# 5_ADC.net
KiCad netlist of a schematic drawn in Altium Designer
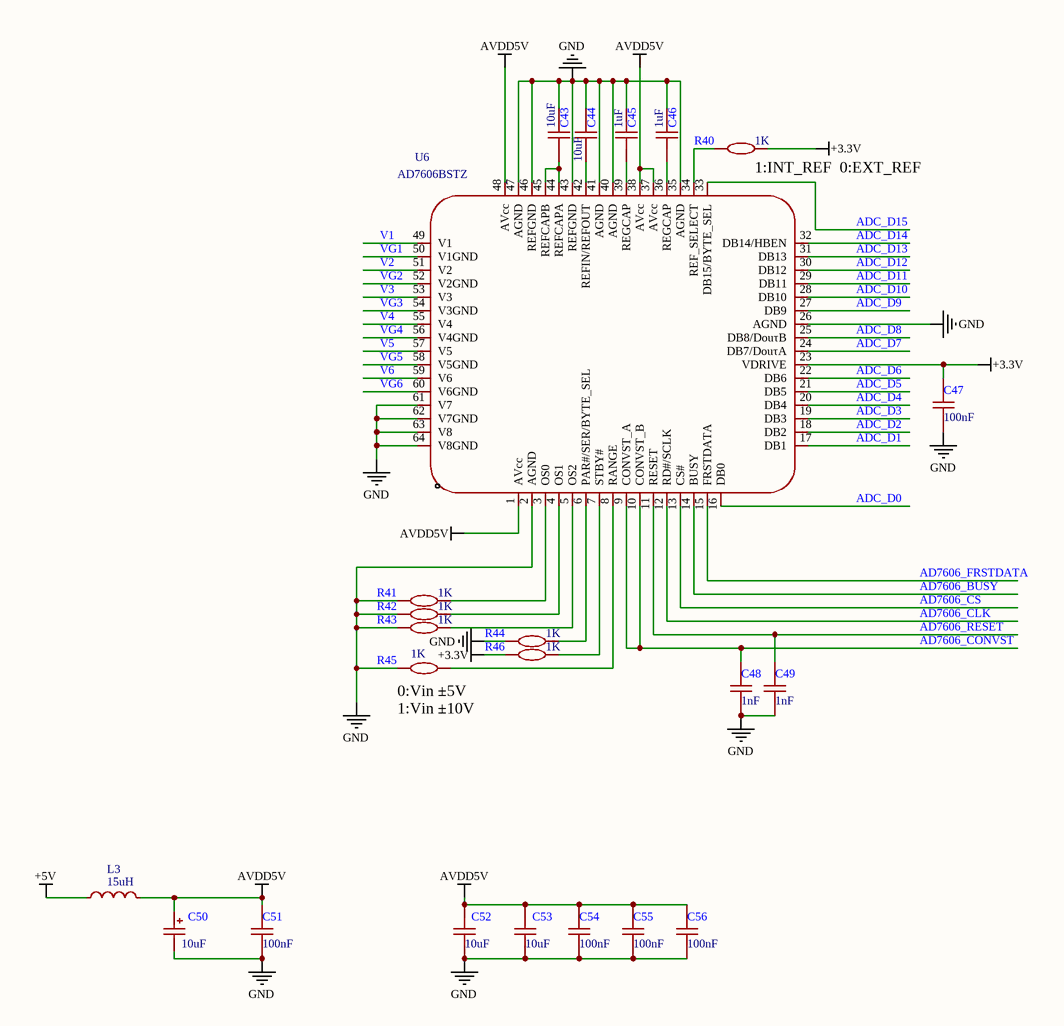
[diagram p0: 5_ADC.schdoc]

(export (version "E")
  (design (tool "Eeschema 10.0.6"))
  (components
    (comp (ref "C43") (value "10uF") (footprint "C0805") (libsource (lib "34567890") (part "CAP_0805")))
    (comp (ref "C44") (value "10uF") (footprint "C0805") (libsource (lib "34567890") (part "CAP_0805")))
    (comp (ref "C45") (value "1uF") (footprint "C0603") (libsource (lib "34567890") (part "CAP_0603")))
    (comp (ref "C46") (value "1uF") (footprint "C0603") (libsource (lib "34567890") (part "CAP_0603")))
    (comp (ref "C47") (value "100nF") (footprint "C0603") (libsource (lib "34567890") (part "CAP_0603")))
    (comp (ref "C48") (value "1nF") (footprint "C0603") (libsource (lib "34567890") (part "CAP_0603")))
    (comp (ref "C49") (value "1nF") (footprint "C0603") (libsource (lib "34567890") (part "CAP_0603")))
    (comp (ref "C50")
      (value "10uF")
      (footprint "C_Ele_SMD_3x5.4mm")
      (libsource (lib "34567890") (part "C_Ele_SMD_3x5.4mm"))
    )
    (comp (ref "C51") (value "100nF") (footprint "C0603") (libsource (lib "34567890") (part "CAP_0603")))
    (comp (ref "C52") (value "10uF") (footprint "C0805") (libsource (lib "34567890") (part "CAP_0805")))
    (comp (ref "C53") (value "10uF") (footprint "C0805") (libsource (lib "34567890") (part "CAP_0805")))
    (comp (ref "C54") (value "100nF") (footprint "C0603") (libsource (lib "34567890") (part "CAP_0603")))
    (comp (ref "C55") (value "100nF") (footprint "C0603") (libsource (lib "34567890") (part "CAP_0603")))
    (comp (ref "C56") (value "100nF") (footprint "C0603") (libsource (lib "34567890") (part "CAP_0603")))
    (comp (ref "L3")
      (value "15uH")
      (footprint "IND-SMD_L7.1-W6.6_SLO0618H")
      (libsource (lib "34567890") (part "SLO0630H150MTT"))
    )
    (comp (ref "R40") (value "1K") (footprint "R0603") (libsource (lib "34567890") (part "Res_0603")))
    (comp (ref "R41") (value "1K") (footprint "R0603") (libsource (lib "34567890") (part "Res_0603")))
    (comp (ref "R42") (value "1K") (footprint "R0603") (libsource (lib "34567890") (part "Res_0603")))
    (comp (ref "R43") (value "1K") (footprint "R0603") (libsource (lib "34567890") (part "Res_0603")))
    (comp (ref "R44") (value "1K") (footprint "R0603") (libsource (lib "34567890") (part "Res_0603")))
    (comp (ref "R45") (value "1K") (footprint "R0603") (libsource (lib "34567890") (part "Res_0603")))
    (comp (ref "R46") (value "1K") (footprint "R0603") (libsource (lib "34567890") (part "Res_0603")))
    (comp (ref "U6")
      (value "AD7606BSTZ")
      (footprint "LQFP-64_L10.0-W10.0-P0.50-LS12.0-BL")
      (libsource (lib "34567890") (part "AD7606BSTZ"))
    )
  )
  (nets
    (net (code "1") (name "+3.3V") (class "Default")
      (node (ref "C47") (pin "2") (pinfunction "2_2") (pintype "passive"))
      (node (ref "R40") (pin "2") (pinfunction "2_2") (pintype "passive"))
      (node (ref "R46") (pin "1") (pinfunction "1_1") (pintype "passive"))
      (node (ref "U6") (pin "23") (pinfunction "VDRIVE_23") (pintype "passive"))
    )
    (net (code "2") (name "+5V") (class "Default")
      (node (ref "L3") (pin "1") (pinfunction "1_1") (pintype "passive"))
    )
    (net (code "3") (name "/AD7606_BUSY") (class "Default")
      (node (ref "U6") (pin "14") (pinfunction "BUSY_14") (pintype "passive"))
    )
    (net (code "4") (name "/AD7606_CLK") (class "Default")
      (node (ref "U6") (pin "12") (pinfunction "RD#/SCLK_12") (pintype "passive"))
    )
    (net (code "5") (name "/AD7606_CONVST") (class "Default")
      (node (ref "C48") (pin "2") (pinfunction "2_2") (pintype "passive"))
      (node (ref "U6") (pin "10") (pinfunction "CONVST_B_10") (pintype "passive"))
      (node (ref "U6") (pin "9") (pinfunction "CONVST_A_9") (pintype "passive"))
    )
    (net (code "6") (name "/AD7606_CS") (class "Default")
      (node (ref "U6") (pin "13") (pinfunction "CS#_13") (pintype "passive"))
    )
    (net (code "7") (name "/AD7606_FRSTDATA") (class "Default")
      (node (ref "U6") (pin "15") (pinfunction "FRSTDATA_15") (pintype "passive"))
    )
    (net (code "8") (name "/AD7606_RESET") (class "Default")
      (node (ref "C49") (pin "2") (pinfunction "2_2") (pintype "passive"))
      (node (ref "U6") (pin "11") (pinfunction "RESET_11") (pintype "passive"))
    )
    (net (code "9") (name "/ADC_D0") (class "Default")
      (node (ref "U6") (pin "16") (pinfunction "DB0_16") (pintype "passive"))
    )
    (net (code "10") (name "/ADC_D1") (class "Default")
      (node (ref "U6") (pin "17") (pinfunction "DB1_17") (pintype "passive"))
    )
    (net (code "11") (name "/ADC_D2") (class "Default")
      (node (ref "U6") (pin "18") (pinfunction "DB2_18") (pintype "passive"))
    )
    (net (code "12") (name "/ADC_D3") (class "Default")
      (node (ref "U6") (pin "19") (pinfunction "DB3_19") (pintype "passive"))
    )
    (net (code "13") (name "/ADC_D4") (class "Default")
      (node (ref "U6") (pin "20") (pinfunction "DB4_20") (pintype "passive"))
    )
    (net (code "14") (name "/ADC_D5") (class "Default")
      (node (ref "U6") (pin "21") (pinfunction "DB5_21") (pintype "passive"))
    )
    (net (code "15") (name "/ADC_D6") (class "Default")
      (node (ref "U6") (pin "22") (pinfunction "DB6_22") (pintype "passive"))
    )
    (net (code "16") (name "/ADC_D7") (class "Default")
      (node (ref "U6") (pin "24") (pinfunction "DB7/DouτA_24") (pintype "passive"))
    )
    (net (code "17") (name "/ADC_D8") (class "Default")
      (node (ref "U6") (pin "25") (pinfunction "DB8/DouτB_25") (pintype "passive"))
    )
    (net (code "18") (name "/ADC_D9") (class "Default")
      (node (ref "U6") (pin "27") (pinfunction "DB9_27") (pintype "passive"))
    )
    (net (code "19") (name "/ADC_D10") (class "Default")
      (node (ref "U6") (pin "28") (pinfunction "DB10_28") (pintype "passive"))
    )
    (net (code "20") (name "/ADC_D11") (class "Default")
      (node (ref "U6") (pin "29") (pinfunction "DB11_29") (pintype "passive"))
    )
    (net (code "21") (name "/ADC_D12") (class "Default")
      (node (ref "U6") (pin "30") (pinfunction "DB12_30") (pintype "passive"))
    )
    (net (code "22") (name "/ADC_D13") (class "Default")
      (node (ref "U6") (pin "31") (pinfunction "DB13_31") (pintype "passive"))
    )
    (net (code "23") (name "/ADC_D14") (class "Default")
      (node (ref "U6") (pin "32") (pinfunction "DB14/HBEN_32") (pintype "passive"))
    )
    (net (code "24") (name "/ADC_D15") (class "Default")
      (node (ref "U6") (pin "33") (pinfunction "DB15/BYTE_SEL_33") (pintype "passive"))
    )
    (net (code "25") (name "/V1") (class "Default")
      (node (ref "U6") (pin "49") (pinfunction "V1_49") (pintype "passive"))
    )
    (net (code "26") (name "/V2") (class "Default")
      (node (ref "U6") (pin "51") (pinfunction "V2_51") (pintype "passive"))
    )
    (net (code "27") (name "/V3") (class "Default")
      (node (ref "U6") (pin "53") (pinfunction "V3_53") (pintype "passive"))
    )
    (net (code "28") (name "/V4") (class "Default")
      (node (ref "U6") (pin "55") (pinfunction "V4_55") (pintype "passive"))
    )
    (net (code "29") (name "/V5") (class "Default")
      (node (ref "U6") (pin "57") (pinfunction "V5_57") (pintype "passive"))
    )
    (net (code "30") (name "/V6") (class "Default")
      (node (ref "U6") (pin "59") (pinfunction "V6_59") (pintype "passive"))
    )
    (net (code "31") (name "/VG1") (class "Default")
      (node (ref "U6") (pin "50") (pinfunction "V1GND_50") (pintype "passive"))
    )
    (net (code "32") (name "/VG2") (class "Default")
      (node (ref "U6") (pin "52") (pinfunction "V2GND_52") (pintype "passive"))
    )
    (net (code "33") (name "/VG3") (class "Default")
      (node (ref "U6") (pin "54") (pinfunction "V3GND_54") (pintype "passive"))
    )
    (net (code "34") (name "/VG4") (class "Default")
      (node (ref "U6") (pin "56") (pinfunction "V4GND_56") (pintype "passive"))
    )
    (net (code "35") (name "/VG5") (class "Default")
      (node (ref "U6") (pin "58") (pinfunction "V5GND_58") (pintype "passive"))
    )
    (net (code "36") (name "/VG6") (class "Default")
      (node (ref "U6") (pin "60") (pinfunction "V6GND_60") (pintype "passive"))
    )
    (net (code "37") (name "AVDD5V") (class "Default")
      (node (ref "C50") (pin "1") (pinfunction "1_1") (pintype "passive"))
      (node (ref "C51") (pin "2") (pinfunction "2_2") (pintype "passive"))
      (node (ref "C52") (pin "2") (pinfunction "2_2") (pintype "passive"))
      (node (ref "C53") (pin "2") (pinfunction "2_2") (pintype "passive"))
      (node (ref "C54") (pin "2") (pinfunction "2_2") (pintype "passive"))
      (node (ref "C55") (pin "2") (pinfunction "2_2") (pintype "passive"))
      (node (ref "C56") (pin "2") (pinfunction "2_2") (pintype "passive"))
      (node (ref "L3") (pin "2") (pinfunction "2_2") (pintype "passive"))
      (node (ref "U6") (pin "1") (pinfunction "AVcc_1") (pintype "passive"))
      (node (ref "U6") (pin "37") (pinfunction "AVcc_37") (pintype "passive"))
      (node (ref "U6") (pin "38") (pinfunction "AVcc_38") (pintype "passive"))
      (node (ref "U6") (pin "48") (pinfunction "AVcc_48") (pintype "passive"))
    )
    (net (code "38") (name "GND") (class "Default")
      (node (ref "C43") (pin "2") (pinfunction "2_2") (pintype "passive"))
      (node (ref "C44") (pin "2") (pinfunction "2_2") (pintype "passive"))
      (node (ref "C45") (pin "2") (pinfunction "2_2") (pintype "passive"))
      (node (ref "C46") (pin "2") (pinfunction "2_2") (pintype "passive"))
      (node (ref "C47") (pin "1") (pinfunction "1_1") (pintype "passive"))
      (node (ref "C48") (pin "1") (pinfunction "1_1") (pintype "passive"))
      (node (ref "C49") (pin "1") (pinfunction "1_1") (pintype "passive"))
      (node (ref "C50") (pin "2") (pinfunction "2_2") (pintype "passive"))
      (node (ref "C51") (pin "1") (pinfunction "1_1") (pintype "passive"))
      (node (ref "C52") (pin "1") (pinfunction "1_1") (pintype "passive"))
      (node (ref "C53") (pin "1") (pinfunction "1_1") (pintype "passive"))
      (node (ref "C54") (pin "1") (pinfunction "1_1") (pintype "passive"))
      (node (ref "C55") (pin "1") (pinfunction "1_1") (pintype "passive"))
      (node (ref "C56") (pin "1") (pinfunction "1_1") (pintype "passive"))
      (node (ref "R41") (pin "1") (pinfunction "1_1") (pintype "passive"))
      (node (ref "R42") (pin "1") (pinfunction "1_1") (pintype "passive"))
      (node (ref "R43") (pin "1") (pinfunction "1_1") (pintype "passive"))
      (node (ref "R44") (pin "1") (pinfunction "1_1") (pintype "passive"))
      (node (ref "R45") (pin "1") (pinfunction "1_1") (pintype "passive"))
      (node (ref "U6") (pin "2") (pinfunction "AGND_2") (pintype "passive"))
      (node (ref "U6") (pin "26") (pinfunction "AGND_26") (pintype "passive"))
      (node (ref "U6") (pin "35") (pinfunction "AGND_35") (pintype "passive"))
      (node (ref "U6") (pin "40") (pinfunction "AGND_40") (pintype "passive"))
      (node (ref "U6") (pin "41") (pinfunction "AGND_41") (pintype "passive"))
      (node (ref "U6") (pin "43") (pinfunction "REFGND_43") (pintype "passive"))
      (node (ref "U6") (pin "46") (pinfunction "REFGND_46") (pintype "passive"))
      (node (ref "U6") (pin "47") (pinfunction "AGND_47") (pintype "passive"))
      (node (ref "U6") (pin "61") (pinfunction "V7_61") (pintype "passive"))
      (node (ref "U6") (pin "62") (pinfunction "V7GND_62") (pintype "passive"))
      (node (ref "U6") (pin "63") (pinfunction "V8_63") (pintype "passive"))
      (node (ref "U6") (pin "64") (pinfunction "V8GND_64") (pintype "passive"))
    )
    (net (code "39") (name "Net-(C45-Pad1)") (class "Default")
      (node (ref "C45") (pin "1") (pinfunction "1_1") (pintype "passive"))
      (node (ref "U6") (pin "39") (pinfunction "REGCAP_39") (pintype "passive"))
    )
    (net (code "40") (name "Net-(C46-Pad1)") (class "Default")
      (node (ref "C46") (pin "1") (pinfunction "1_1") (pintype "passive"))
      (node (ref "U6") (pin "36") (pinfunction "REGCAP_36") (pintype "passive"))
    )
    (net (code "41") (name "Net-(U6-OS0)") (class "Default")
      (node (ref "R41") (pin "2") (pinfunction "2_2") (pintype "passive"))
      (node (ref "U6") (pin "3") (pinfunction "OS0_3") (pintype "passive"))
    )
    (net (code "42") (name "Net-(U6-OS1)") (class "Default")
      (node (ref "R42") (pin "2") (pinfunction "2_2") (pintype "passive"))
      (node (ref "U6") (pin "4") (pinfunction "OS1_4") (pintype "passive"))
    )
    (net (code "43") (name "Net-(U6-OS2)") (class "Default")
      (node (ref "R43") (pin "2") (pinfunction "2_2") (pintype "passive"))
      (node (ref "U6") (pin "5") (pinfunction "OS2_5") (pintype "passive"))
    )
    (net (code "44") (name "Net-(U6-PAR#{slash}SER{slash}BYTE_SEL)") (class "Default")
      (node (ref "R44") (pin "2") (pinfunction "2_2") (pintype "passive"))
      (node (ref "U6") (pin "6") (pinfunction "PAR#/SER/BYTE_SEL_6") (pintype "passive"))
    )
    (net (code "45") (name "Net-(U6-RANGE)") (class "Default")
      (node (ref "R45") (pin "2") (pinfunction "2_2") (pintype "passive"))
      (node (ref "U6") (pin "8") (pinfunction "RANGE_8") (pintype "passive"))
    )
    (net (code "46") (name "Net-(U6-REFCAPA)") (class "Default")
      (node (ref "C43") (pin "1") (pinfunction "1_1") (pintype "passive"))
      (node (ref "U6") (pin "44") (pinfunction "REFCAPA_44") (pintype "passive"))
      (node (ref "U6") (pin "45") (pinfunction "REFCAPB_45") (pintype "passive"))
    )
    (net (code "47") (name "Net-(U6-REFIN{slash}REFOUT)") (class "Default")
      (node (ref "C44") (pin "1") (pinfunction "1_1") (pintype "passive"))
      (node (ref "U6") (pin "42") (pinfunction "REFIN/REFOUT_42") (pintype "passive"))
    )
    (net (code "48") (name "Net-(U6-REF_SELECT)") (class "Default")
      (node (ref "R40") (pin "1") (pinfunction "1_1") (pintype "passive"))
      (node (ref "U6") (pin "34") (pinfunction "REF_SELECT_34") (pintype "passive"))
    )
    (net (code "49") (name "Net-(U6-STBY#)") (class "Default")
      (node (ref "R46") (pin "2") (pinfunction "2_2") (pintype "passive"))
      (node (ref "U6") (pin "7") (pinfunction "STBY#_7") (pintype "passive"))
    )
  )
)
